# kg_op_ubtb.net
KiCad netlist of a schematic drawn in EAGLE
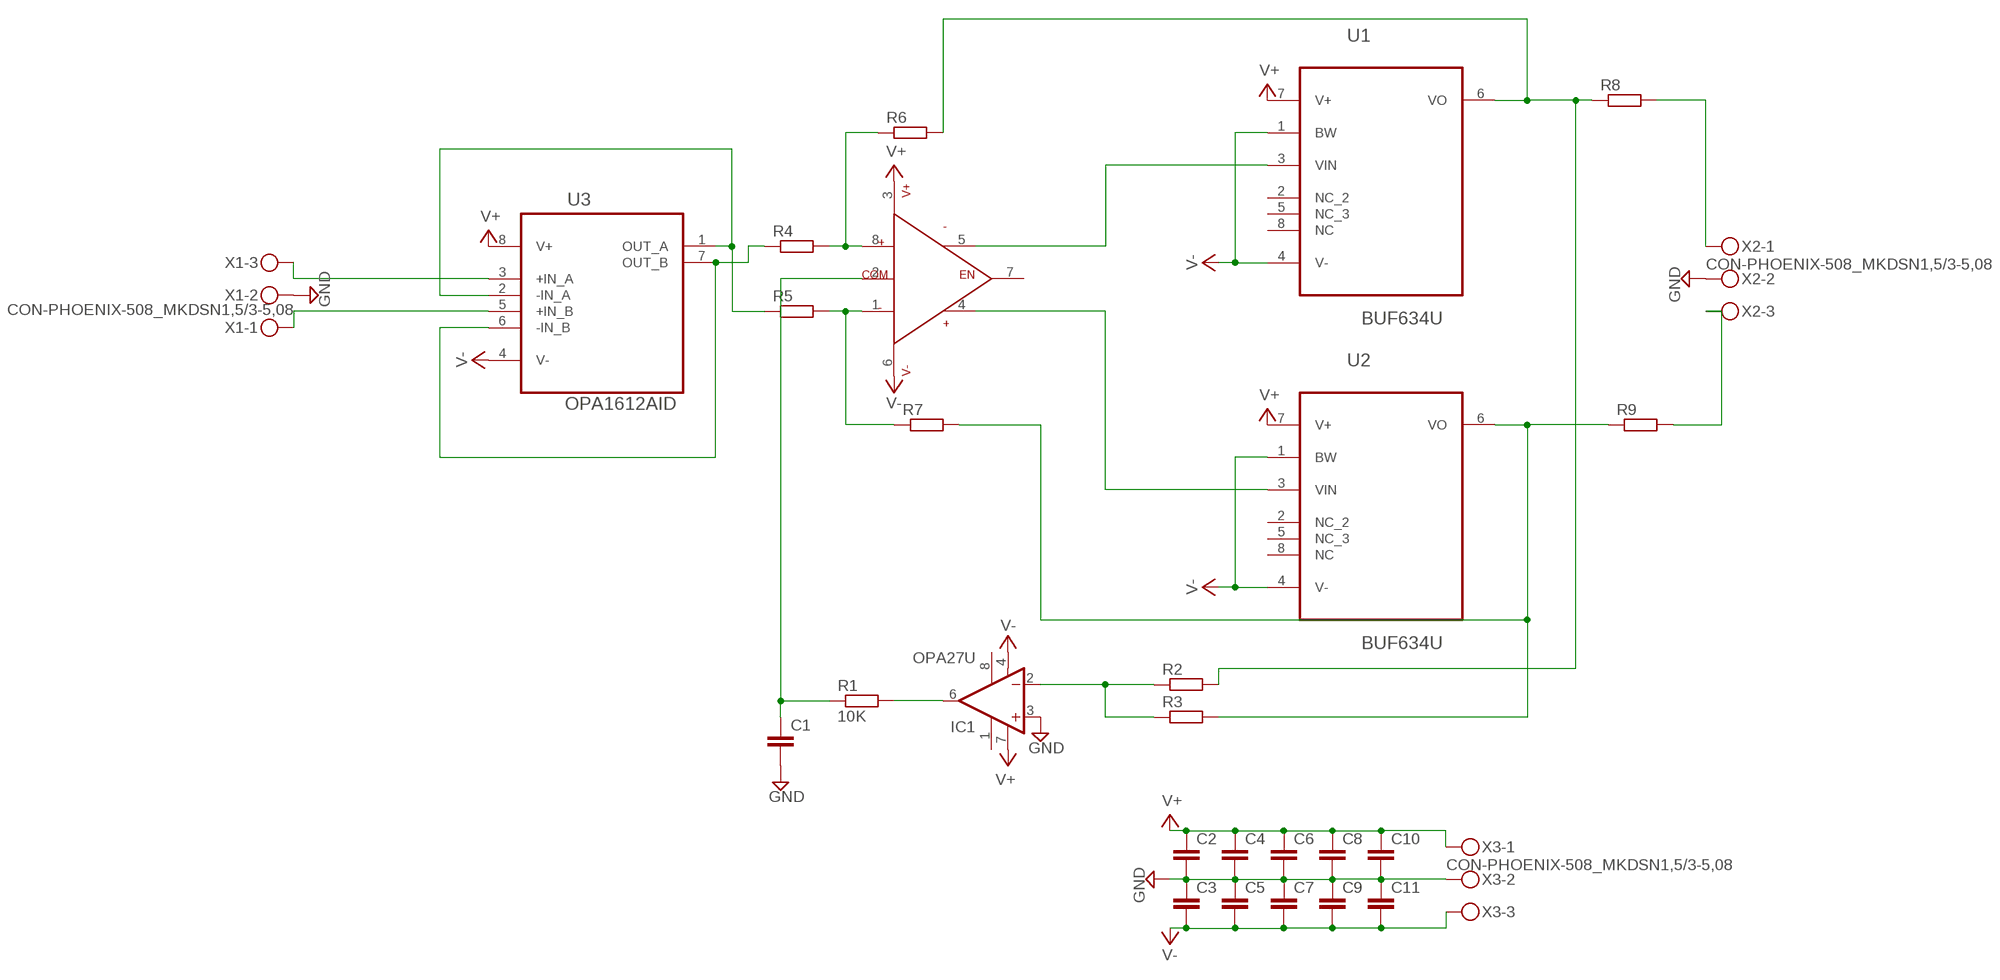
[diagram p0: schematic, sheet 1]

(export (version "E")
  (design (tool "Eeschema 10.0.6"))
  (components
    (comp (ref "C1")
      (value "C-EUC0805")
      (footprint "eagle-import:C0805")
      (libsource (lib "eagle-import") (part "C-EUC0805"))
    )
    (comp (ref "C2")
      (value "C-EUC0805")
      (footprint "eagle-import:C0805")
      (libsource (lib "eagle-import") (part "C-EUC0805"))
    )
    (comp (ref "C3")
      (value "C-EUC0805")
      (footprint "eagle-import:C0805")
      (libsource (lib "eagle-import") (part "C-EUC0805"))
    )
    (comp (ref "C4")
      (value "C-EUC0805")
      (footprint "eagle-import:C0805")
      (libsource (lib "eagle-import") (part "C-EUC0805"))
    )
    (comp (ref "C5")
      (value "C-EUC0805")
      (footprint "eagle-import:C0805")
      (libsource (lib "eagle-import") (part "C-EUC0805"))
    )
    (comp (ref "C6")
      (value "C-EUC0805")
      (footprint "eagle-import:C0805")
      (libsource (lib "eagle-import") (part "C-EUC0805"))
    )
    (comp (ref "C7")
      (value "C-EUC0805")
      (footprint "eagle-import:C0805")
      (libsource (lib "eagle-import") (part "C-EUC0805"))
    )
    (comp (ref "C8")
      (value "C-EUC0805")
      (footprint "eagle-import:C0805")
      (libsource (lib "eagle-import") (part "C-EUC0805"))
    )
    (comp (ref "C9")
      (value "C-EUC0805")
      (footprint "eagle-import:C0805")
      (libsource (lib "eagle-import") (part "C-EUC0805"))
    )
    (comp (ref "C10")
      (value "C-EUC0805")
      (footprint "eagle-import:C0805")
      (libsource (lib "eagle-import") (part "C-EUC0805"))
    )
    (comp (ref "C11")
      (value "C-EUC0805")
      (footprint "eagle-import:C0805")
      (libsource (lib "eagle-import") (part "C-EUC0805"))
    )
    (comp (ref "IC1")
      (value "OPA27U")
      (footprint "eagle-import:SO08")
      (libsource (lib "eagle-import") (part "OPA?U27"))
    )
    (comp (ref "R1")
      (value "10K")
      (footprint "eagle-import:MINI_MELF-0204W")
      (libsource (lib "eagle-import") (part "R-EU_MELF0204W"))
    )
    (comp (ref "R2")
      (value "R-EU_MELF0204W")
      (footprint "eagle-import:MINI_MELF-0204W")
      (libsource (lib "eagle-import") (part "R-EU_MELF0204W"))
    )
    (comp (ref "R3")
      (value "R-EU_MELF0204W")
      (footprint "eagle-import:MINI_MELF-0204W")
      (libsource (lib "eagle-import") (part "R-EU_MELF0204W"))
    )
    (comp (ref "R4")
      (value "R-EU_MELF0204W")
      (footprint "eagle-import:MINI_MELF-0204W")
      (libsource (lib "eagle-import") (part "R-EU_MELF0204W"))
    )
    (comp (ref "R5")
      (value "R-EU_MELF0204W")
      (footprint "eagle-import:MINI_MELF-0204W")
      (libsource (lib "eagle-import") (part "R-EU_MELF0204W"))
    )
    (comp (ref "R6")
      (value "R-EU_MELF0204W")
      (footprint "eagle-import:MINI_MELF-0204W")
      (libsource (lib "eagle-import") (part "R-EU_MELF0204W"))
    )
    (comp (ref "R7")
      (value "R-EU_MELF0204W")
      (footprint "eagle-import:MINI_MELF-0204W")
      (libsource (lib "eagle-import") (part "R-EU_MELF0204W"))
    )
    (comp (ref "R8")
      (value "R-EU_MELF0204W")
      (footprint "eagle-import:MINI_MELF-0204W")
      (libsource (lib "eagle-import") (part "R-EU_MELF0204W"))
    )
    (comp (ref "R9")
      (value "R-EU_MELF0204W")
      (footprint "eagle-import:MINI_MELF-0204W")
      (libsource (lib "eagle-import") (part "R-EU_MELF0204W"))
    )
    (comp (ref "U$1")
      (value "OPA1632")
      (footprint "eagle-import:SO8")
      (libsource (lib "eagle-import") (part "OPA1632"))
    )
    (comp (ref "U1")
      (value "BUF634U")
      (footprint "eagle-import:SOIC127P600X175-8N")
      (libsource (lib "eagle-import") (part "BUF634U"))
    )
    (comp (ref "U2")
      (value "BUF634U")
      (footprint "eagle-import:SOIC127P600X175-8N")
      (libsource (lib "eagle-import") (part "BUF634U"))
    )
    (comp (ref "U3")
      (value "OPA1612AID")
      (footprint "eagle-import:SOIC127P600X175-8N")
      (libsource (lib "eagle-import") (part "OPA1612AID"))
    )
    (comp (ref "X1")
      (value "CON-PHOENIX-508_MKDSN1,5/3-5,08")
      (footprint "eagle-import:CON-PHOENIX-508_MKDSN1,5_3-5,08")
      (libsource (lib "eagle-import") (part "CON-PHOENIX-508_MKDSN1,5/3-5,08"))
    )
    (comp (ref "X2")
      (value "CON-PHOENIX-508_MKDSN1,5/3-5,08")
      (footprint "eagle-import:CON-PHOENIX-508_MKDSN1,5_3-5,08")
      (libsource (lib "eagle-import") (part "CON-PHOENIX-508_MKDSN1,5/3-5,08"))
    )
    (comp (ref "X3")
      (value "CON-PHOENIX-508_MKDSN1,5/3-5,08")
      (footprint "eagle-import:CON-PHOENIX-508_MKDSN1,5_3-5,08")
      (libsource (lib "eagle-import") (part "CON-PHOENIX-508_MKDSN1,5/3-5,08"))
    )
  )
  (nets
    (net (code "1") (name "GND") (class "Default")
      (node (ref "C1") (pin "2") (pinfunction "2_2") (pintype "passive"))
      (node (ref "C10") (pin "2") (pinfunction "2_2") (pintype "passive"))
      (node (ref "C11") (pin "1") (pinfunction "1_1") (pintype "passive"))
      (node (ref "C2") (pin "2") (pinfunction "2_2") (pintype "passive"))
      (node (ref "C3") (pin "1") (pinfunction "1_1") (pintype "passive"))
      (node (ref "C4") (pin "2") (pinfunction "2_2") (pintype "passive"))
      (node (ref "C5") (pin "1") (pinfunction "1_1") (pintype "passive"))
      (node (ref "C6") (pin "2") (pinfunction "2_2") (pintype "passive"))
      (node (ref "C7") (pin "1") (pinfunction "1_1") (pintype "passive"))
      (node (ref "C8") (pin "2") (pinfunction "2_2") (pintype "passive"))
      (node (ref "C9") (pin "1") (pinfunction "1_1") (pintype "passive"))
      (node (ref "IC1") (pin "3") (pinfunction "+IN_3") (pintype "input"))
      (node (ref "X1") (pin "2") (pinfunction "KL_2") (pintype "passive"))
      (node (ref "X2") (pin "2") (pinfunction "KL_2") (pintype "passive"))
      (node (ref "X3") (pin "2") (pinfunction "KL_2") (pintype "passive"))
    )
    (net (code "2") (name "Net-(IC1--IN)") (class "Default")
      (node (ref "IC1") (pin "2") (pinfunction "-IN_2") (pintype "input"))
      (node (ref "R2") (pin "1") (pinfunction "1_1") (pintype "passive"))
      (node (ref "R3") (pin "1") (pinfunction "1_1") (pintype "passive"))
    )
    (net (code "3") (name "Net-(IC1-OUT)") (class "Default")
      (node (ref "IC1") (pin "6") (pinfunction "OUT_6") (pintype "output"))
      (node (ref "R1") (pin "2") (pinfunction "2_2") (pintype "passive"))
    )
    (net (code "4") (name "Net-(U$1-COM)") (class "Default")
      (node (ref "C1") (pin "1") (pinfunction "1_1") (pintype "passive"))
      (node (ref "R1") (pin "1") (pinfunction "1_1") (pintype "passive"))
      (node (ref "U$1") (pin "2") (pinfunction "COM_2") (pintype "bidirectional"))
    )
    (net (code "5") (name "Net-(U$1-IN+)") (class "Default")
      (node (ref "R4") (pin "2") (pinfunction "2_2") (pintype "passive"))
      (node (ref "R6") (pin "1") (pinfunction "1_1") (pintype "passive"))
      (node (ref "U$1") (pin "8") (pinfunction "IN+_8") (pintype "bidirectional"))
    )
    (net (code "6") (name "Net-(U$1-IN-)") (class "Default")
      (node (ref "R5") (pin "2") (pinfunction "2_2") (pintype "passive"))
      (node (ref "R7") (pin "1") (pinfunction "1_1") (pintype "passive"))
      (node (ref "U$1") (pin "1") (pinfunction "IN-_1") (pintype "bidirectional"))
    )
    (net (code "7") (name "Net-(U$1-OUT+)") (class "Default")
      (node (ref "U$1") (pin "4") (pinfunction "OUT+_4") (pintype "bidirectional"))
      (node (ref "U2") (pin "3") (pinfunction "VIN_3") (pintype "input"))
    )
    (net (code "8") (name "Net-(U$1-OUT-)") (class "Default")
      (node (ref "U$1") (pin "5") (pinfunction "OUT-_5") (pintype "bidirectional"))
      (node (ref "U1") (pin "3") (pinfunction "VIN_3") (pintype "input"))
    )
    (net (code "9") (name "Net-(U1-VO)") (class "Default")
      (node (ref "R2") (pin "2") (pinfunction "2_2") (pintype "passive"))
      (node (ref "R6") (pin "2") (pinfunction "2_2") (pintype "passive"))
      (node (ref "R8") (pin "1") (pinfunction "1_1") (pintype "passive"))
      (node (ref "U1") (pin "6") (pinfunction "VO_6") (pintype "output"))
    )
    (net (code "10") (name "Net-(U2-VO)") (class "Default")
      (node (ref "R3") (pin "2") (pinfunction "2_2") (pintype "passive"))
      (node (ref "R7") (pin "2") (pinfunction "2_2") (pintype "passive"))
      (node (ref "R9") (pin "1") (pinfunction "1_1") (pintype "passive"))
      (node (ref "U2") (pin "6") (pinfunction "VO_6") (pintype "output"))
    )
    (net (code "11") (name "Net-(U3-+IN_A)") (class "Default")
      (node (ref "U3") (pin "3") (pinfunction "+IN_A_3") (pintype "input"))
      (node (ref "X1") (pin "3") (pinfunction "KL_3") (pintype "passive"))
    )
    (net (code "12") (name "Net-(U3-+IN_B)") (class "Default")
      (node (ref "U3") (pin "5") (pinfunction "+IN_B_5") (pintype "input"))
      (node (ref "X1") (pin "1") (pinfunction "KL_1") (pintype "passive"))
    )
    (net (code "13") (name "Net-(U3--IN_A)") (class "Default")
      (node (ref "R5") (pin "1") (pinfunction "1_1") (pintype "passive"))
      (node (ref "U3") (pin "1") (pinfunction "OUT_A_1") (pintype "output"))
      (node (ref "U3") (pin "2") (pinfunction "-IN_A_2") (pintype "input"))
    )
    (net (code "14") (name "Net-(U3--IN_B)") (class "Default")
      (node (ref "R4") (pin "1") (pinfunction "1_1") (pintype "passive"))
      (node (ref "U3") (pin "6") (pinfunction "-IN_B_6") (pintype "input"))
      (node (ref "U3") (pin "7") (pinfunction "OUT_B_7") (pintype "output"))
    )
    (net (code "15") (name "Net-(X2A-KL)") (class "Default")
      (node (ref "R8") (pin "2") (pinfunction "2_2") (pintype "passive"))
      (node (ref "X2") (pin "1") (pinfunction "KL_1") (pintype "passive"))
    )
    (net (code "16") (name "Net-(X2C-KL)") (class "Default")
      (node (ref "R9") (pin "2") (pinfunction "2_2") (pintype "passive"))
      (node (ref "X2") (pin "3") (pinfunction "KL_3") (pintype "passive"))
    )
    (net (code "17") (name "V+") (class "Default")
      (node (ref "C10") (pin "1") (pinfunction "1_1") (pintype "passive"))
      (node (ref "C2") (pin "1") (pinfunction "1_1") (pintype "passive"))
      (node (ref "C4") (pin "1") (pinfunction "1_1") (pintype "passive"))
      (node (ref "C6") (pin "1") (pinfunction "1_1") (pintype "passive"))
      (node (ref "C8") (pin "1") (pinfunction "1_1") (pintype "passive"))
      (node (ref "IC1") (pin "7") (pinfunction "V+_7") (pintype "power_in"))
      (node (ref "U$1") (pin "3") (pinfunction "V+_3") (pintype "bidirectional"))
      (node (ref "U1") (pin "7") (pinfunction "V+_7") (pintype "power_in"))
      (node (ref "U2") (pin "7") (pinfunction "V+_7") (pintype "power_in"))
      (node (ref "U3") (pin "8") (pinfunction "V+_8") (pintype "power_in"))
      (node (ref "X3") (pin "1") (pinfunction "KL_1") (pintype "passive"))
    )
    (net (code "18") (name "V-") (class "Default")
      (node (ref "C11") (pin "2") (pinfunction "2_2") (pintype "passive"))
      (node (ref "C3") (pin "2") (pinfunction "2_2") (pintype "passive"))
      (node (ref "C5") (pin "2") (pinfunction "2_2") (pintype "passive"))
      (node (ref "C7") (pin "2") (pinfunction "2_2") (pintype "passive"))
      (node (ref "C9") (pin "2") (pinfunction "2_2") (pintype "passive"))
      (node (ref "IC1") (pin "4") (pinfunction "V-_4") (pintype "power_in"))
      (node (ref "U$1") (pin "6") (pinfunction "V-_6") (pintype "bidirectional"))
      (node (ref "U1") (pin "1") (pinfunction "BW_1") (pintype "passive"))
      (node (ref "U1") (pin "4") (pinfunction "V-_4") (pintype "power_in"))
      (node (ref "U2") (pin "1") (pinfunction "BW_1") (pintype "passive"))
      (node (ref "U2") (pin "4") (pinfunction "V-_4") (pintype "power_in"))
      (node (ref "U3") (pin "4") (pinfunction "V-_4") (pintype "power_in"))
      (node (ref "X3") (pin "3") (pinfunction "KL_3") (pintype "passive"))
    )
    (net (code "19") (name "unconnected-(IC1-OFF1-Pad1)") (class "Default")
      (node (ref "IC1") (pin "1") (pinfunction "OFF1_1") (pintype "passive"))
    )
    (net (code "20") (name "unconnected-(IC1-OFF2-Pad8)") (class "Default")
      (node (ref "IC1") (pin "8") (pinfunction "OFF2_8") (pintype "passive"))
    )
    (net (code "21") (name "unconnected-(U$1-EN-Pad7)") (class "Default")
      (node (ref "U$1") (pin "7") (pinfunction "EN_7") (pintype "bidirectional"))
    )
    (net (code "22") (name "unconnected-(U1-NC-Pad8)") (class "Default")
      (node (ref "U1") (pin "8") (pinfunction "NC_8") (pintype "no_connect"))
    )
    (net (code "23") (name "unconnected-(U1-NC_2-Pad2)") (class "Default")
      (node (ref "U1") (pin "2") (pinfunction "NC_2_2") (pintype "no_connect"))
    )
    (net (code "24") (name "unconnected-(U1-NC_3-Pad5)") (class "Default")
      (node (ref "U1") (pin "5") (pinfunction "NC_3_5") (pintype "no_connect"))
    )
    (net (code "25") (name "unconnected-(U2-NC-Pad8)") (class "Default")
      (node (ref "U2") (pin "8") (pinfunction "NC_8") (pintype "no_connect"))
    )
    (net (code "26") (name "unconnected-(U2-NC_2-Pad2)") (class "Default")
      (node (ref "U2") (pin "2") (pinfunction "NC_2_2") (pintype "no_connect"))
    )
    (net (code "27") (name "unconnected-(U2-NC_3-Pad5)") (class "Default")
      (node (ref "U2") (pin "5") (pinfunction "NC_3_5") (pintype "no_connect"))
    )
  )
)
